# pax_counter.net
KiCad netlist of a schematic drawn in EAGLE
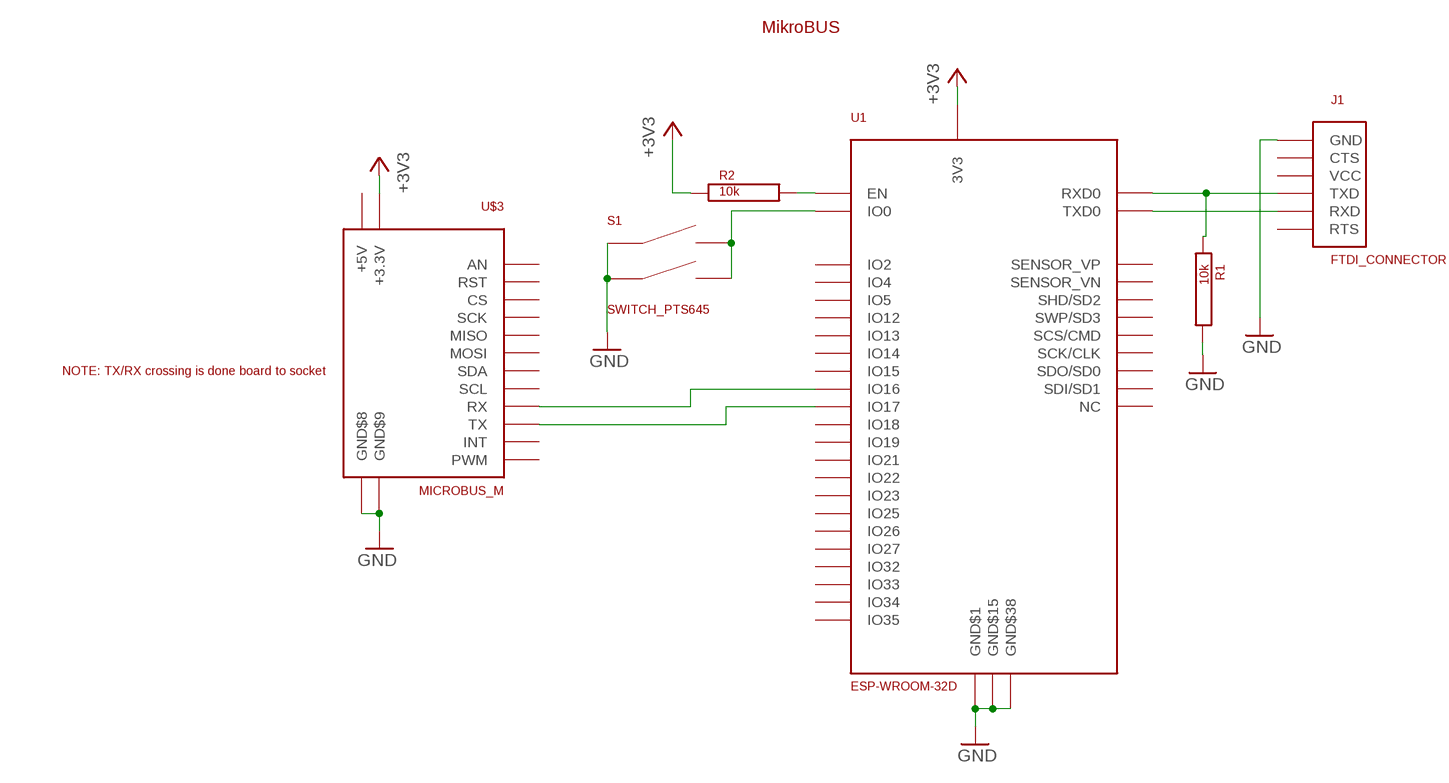
[diagram p0: schematic, sheet 1]

(export (version "E")
  (design (tool "Eeschema 10.0.6"))
  (components
    (comp (ref "J1")
      (value "FTDI_CONNECTOR")
      (footprint "eagle-import:FTDI_CONNECTOR")
      (libsource (lib "eagle-import") (part "FTDI_CONNECTOR"))
    )
    (comp (ref "R1")
      (value "10k")
      (footprint "eagle-import:RES_0402")
      (libsource (lib "eagle-import") (part "RESISTOR"))
    )
    (comp (ref "R2")
      (value "10k")
      (footprint "eagle-import:RES_0402")
      (libsource (lib "eagle-import") (part "RESISTOR"))
    )
    (comp (ref "S1")
      (value "SWITCH_PTS645")
      (footprint "eagle-import:SWITCH_PTS645_EE_NBIOT_01")
      (libsource (lib "eagle-import") (part "SWITCH_PTS645"))
    )
    (comp (ref "U$1")
      (value "MIKROBUS_LOGO")
      (footprint "eagle-import:MIKROBUS_LOGO")
      (libsource (lib "eagle-import") (part "MIKROBUS_LOGO"))
    )
    (comp (ref "U$3")
      (value "MICROBUS_M")
      (footprint "eagle-import:MIKROBUS_M")
      (libsource (lib "eagle-import") (part "MICROBUS_M"))
    )
    (comp (ref "U1")
      (value "ESP-WROOM-32D")
      (footprint "eagle-import:ESP_WROOM_32D")
      (libsource (lib "eagle-import") (part "ESP-WROOM-32D"))
    )
  )
  (nets
    (net (code "1") (name "+3V3") (class "Default")
      (node (ref "R2") (pin "P$1") (pinfunction "P$1_P$1") (pintype "bidirectional"))
      (node (ref "U$3") (pin "+3.3V") (pinfunction "+3.3V_+3.3V") (pintype "bidirectional"))
      (node (ref "U1") (pin "2") (pinfunction "3V3_2") (pintype "bidirectional"))
    )
    (net (code "2") (name "GND") (class "Default")
      (node (ref "J1") (pin "GND") (pinfunction "GND_GND") (pintype "bidirectional"))
      (node (ref "R1") (pin "P$2") (pinfunction "P$2_P$2") (pintype "bidirectional"))
      (node (ref "S1") (pin "A1") (pinfunction "A1_A1") (pintype "bidirectional"))
      (node (ref "S1") (pin "A2") (pinfunction "A2_A2") (pintype "bidirectional"))
      (node (ref "U$3") (pin "GND$8") (pinfunction "GND$8_GND$8") (pintype "bidirectional"))
      (node (ref "U$3") (pin "GND$9") (pinfunction "GND$9_GND$9") (pintype "bidirectional"))
      (node (ref "U1") (pin "1") (pinfunction "GND$1_1") (pintype "bidirectional"))
      (node (ref "U1") (pin "15") (pinfunction "GND$15_15") (pintype "bidirectional"))
      (node (ref "U1") (pin "38") (pinfunction "GND$38_38") (pintype "bidirectional"))
      (node (ref "U1") (pin "GND$39") (pinfunction "GND$38_GND$39") (pintype "bidirectional"))
      (node (ref "U1") (pin "GND$40") (pinfunction "GND$38_GND$40") (pintype "bidirectional"))
      (node (ref "U1") (pin "GND$41") (pinfunction "GND$38_GND$41") (pintype "bidirectional"))
      (node (ref "U1") (pin "GND$42") (pinfunction "GND$38_GND$42") (pintype "bidirectional"))
      (node (ref "U1") (pin "GND$43") (pinfunction "GND$38_GND$43") (pintype "bidirectional"))
      (node (ref "U1") (pin "GND$44") (pinfunction "GND$38_GND$44") (pintype "bidirectional"))
      (node (ref "U1") (pin "GND$45") (pinfunction "GND$38_GND$45") (pintype "bidirectional"))
      (node (ref "U1") (pin "GND$46") (pinfunction "GND$38_GND$46") (pintype "bidirectional"))
      (node (ref "U1") (pin "GND$47") (pinfunction "GND$38_GND$47") (pintype "bidirectional"))
    )
    (net (code "3") (name "Net-(U1-EN)") (class "Default")
      (node (ref "R2") (pin "P$2") (pinfunction "P$2_P$2") (pintype "bidirectional"))
      (node (ref "U1") (pin "3") (pinfunction "EN_3") (pintype "bidirectional"))
    )
    (net (code "4") (name "Net-(U1-IO0)") (class "Default")
      (node (ref "S1") (pin "B1") (pinfunction "B1_B1") (pintype "bidirectional"))
      (node (ref "S1") (pin "B2") (pinfunction "B2_B2") (pintype "bidirectional"))
      (node (ref "U1") (pin "25") (pinfunction "IO0_25") (pintype "bidirectional"))
    )
    (net (code "5") (name "Net-(U1-IO16)") (class "Default")
      (node (ref "U$3") (pin "RX") (pinfunction "RX_RX") (pintype "bidirectional"))
      (node (ref "U1") (pin "27") (pinfunction "IO16_27") (pintype "bidirectional"))
    )
    (net (code "6") (name "Net-(U1-IO17)") (class "Default")
      (node (ref "U$3") (pin "TX") (pinfunction "TX_TX") (pintype "bidirectional"))
      (node (ref "U1") (pin "28") (pinfunction "IO17_28") (pintype "bidirectional"))
    )
    (net (code "7") (name "Net-(U1-RXD0)") (class "Default")
      (node (ref "J1") (pin "TXD") (pinfunction "TXD_TXD") (pintype "bidirectional"))
      (node (ref "R1") (pin "P$1") (pinfunction "P$1_P$1") (pintype "bidirectional"))
      (node (ref "U1") (pin "34") (pinfunction "RXD0_34") (pintype "bidirectional"))
    )
    (net (code "8") (name "Net-(U1-TXD0)") (class "Default")
      (node (ref "J1") (pin "RXD") (pinfunction "RXD_RXD") (pintype "bidirectional"))
      (node (ref "U1") (pin "35") (pinfunction "TXD0_35") (pintype "bidirectional"))
    )
    (net (code "9") (name "unconnected-(J1-PadCTS)") (class "Default")
      (node (ref "J1") (pin "CTS") (pinfunction "CTS_CTS") (pintype "bidirectional"))
    )
    (net (code "10") (name "unconnected-(J1-PadRTS)") (class "Default")
      (node (ref "J1") (pin "RTS") (pinfunction "RTS_RTS") (pintype "bidirectional"))
    )
    (net (code "11") (name "unconnected-(J1-PadVCC)") (class "Default")
      (node (ref "J1") (pin "VCC") (pinfunction "VCC_VCC") (pintype "bidirectional"))
    )
    (net (code "12") (name "unconnected-(U$3-Pad+5V)") (class "Default")
      (node (ref "U$3") (pin "+5V") (pinfunction "+5V_+5V") (pintype "bidirectional"))
    )
    (net (code "13") (name "unconnected-(U$3-PadAN)") (class "Default")
      (node (ref "U$3") (pin "AN") (pinfunction "AN_AN") (pintype "bidirectional"))
    )
    (net (code "14") (name "unconnected-(U$3-PadCS)") (class "Default")
      (node (ref "U$3") (pin "CS") (pinfunction "CS_CS") (pintype "bidirectional"))
    )
    (net (code "15") (name "unconnected-(U$3-PadINT)") (class "Default")
      (node (ref "U$3") (pin "INT") (pinfunction "INT_INT") (pintype "bidirectional"))
    )
    (net (code "16") (name "unconnected-(U$3-PadMISO)") (class "Default")
      (node (ref "U$3") (pin "MISO") (pinfunction "MISO_MISO") (pintype "bidirectional"))
    )
    (net (code "17") (name "unconnected-(U$3-PadMOSI)") (class "Default")
      (node (ref "U$3") (pin "MOSI") (pinfunction "MOSI_MOSI") (pintype "bidirectional"))
    )
    (net (code "18") (name "unconnected-(U$3-PadPWM)") (class "Default")
      (node (ref "U$3") (pin "PWM") (pinfunction "PWM_PWM") (pintype "bidirectional"))
    )
    (net (code "19") (name "unconnected-(U$3-PadRST)") (class "Default")
      (node (ref "U$3") (pin "RST") (pinfunction "RST_RST") (pintype "bidirectional"))
    )
    (net (code "20") (name "unconnected-(U$3-PadSCK)") (class "Default")
      (node (ref "U$3") (pin "SCK") (pinfunction "SCK_SCK") (pintype "bidirectional"))
    )
    (net (code "21") (name "unconnected-(U$3-PadSCL)") (class "Default")
      (node (ref "U$3") (pin "SCL") (pinfunction "SCL_SCL") (pintype "bidirectional"))
    )
    (net (code "22") (name "unconnected-(U$3-PadSDA)") (class "Default")
      (node (ref "U$3") (pin "SDA") (pinfunction "SDA_SDA") (pintype "bidirectional"))
    )
    (net (code "23") (name "unconnected-(U1-IO2-Pad24)") (class "Default")
      (node (ref "U1") (pin "24") (pinfunction "IO2_24") (pintype "bidirectional"))
    )
    (net (code "24") (name "unconnected-(U1-IO4-Pad26)") (class "Default")
      (node (ref "U1") (pin "26") (pinfunction "IO4_26") (pintype "bidirectional"))
    )
    (net (code "25") (name "unconnected-(U1-IO5-Pad29)") (class "Default")
      (node (ref "U1") (pin "29") (pinfunction "IO5_29") (pintype "bidirectional"))
    )
    (net (code "26") (name "unconnected-(U1-IO12-Pad14)") (class "Default")
      (node (ref "U1") (pin "14") (pinfunction "IO12_14") (pintype "bidirectional"))
    )
    (net (code "27") (name "unconnected-(U1-IO13-Pad16)") (class "Default")
      (node (ref "U1") (pin "16") (pinfunction "IO13_16") (pintype "bidirectional"))
    )
    (net (code "28") (name "unconnected-(U1-IO14-Pad13)") (class "Default")
      (node (ref "U1") (pin "13") (pinfunction "IO14_13") (pintype "bidirectional"))
    )
    (net (code "29") (name "unconnected-(U1-IO15-Pad23)") (class "Default")
      (node (ref "U1") (pin "23") (pinfunction "IO15_23") (pintype "bidirectional"))
    )
    (net (code "30") (name "unconnected-(U1-IO18-Pad30)") (class "Default")
      (node (ref "U1") (pin "30") (pinfunction "IO18_30") (pintype "bidirectional"))
    )
    (net (code "31") (name "unconnected-(U1-IO19-Pad31)") (class "Default")
      (node (ref "U1") (pin "31") (pinfunction "IO19_31") (pintype "bidirectional"))
    )
    (net (code "32") (name "unconnected-(U1-IO21-Pad33)") (class "Default")
      (node (ref "U1") (pin "33") (pinfunction "IO21_33") (pintype "bidirectional"))
    )
    (net (code "33") (name "unconnected-(U1-IO22-Pad36)") (class "Default")
      (node (ref "U1") (pin "36") (pinfunction "IO22_36") (pintype "bidirectional"))
    )
    (net (code "34") (name "unconnected-(U1-IO23-Pad37)") (class "Default")
      (node (ref "U1") (pin "37") (pinfunction "IO23_37") (pintype "bidirectional"))
    )
    (net (code "35") (name "unconnected-(U1-IO25-Pad10)") (class "Default")
      (node (ref "U1") (pin "10") (pinfunction "IO25_10") (pintype "bidirectional"))
    )
    (net (code "36") (name "unconnected-(U1-IO26-Pad11)") (class "Default")
      (node (ref "U1") (pin "11") (pinfunction "IO26_11") (pintype "bidirectional"))
    )
    (net (code "37") (name "unconnected-(U1-IO27-Pad12)") (class "Default")
      (node (ref "U1") (pin "12") (pinfunction "IO27_12") (pintype "bidirectional"))
    )
    (net (code "38") (name "unconnected-(U1-IO32-Pad8)") (class "Default")
      (node (ref "U1") (pin "8") (pinfunction "IO32_8") (pintype "bidirectional"))
    )
    (net (code "39") (name "unconnected-(U1-IO33-Pad9)") (class "Default")
      (node (ref "U1") (pin "9") (pinfunction "IO33_9") (pintype "bidirectional"))
    )
    (net (code "40") (name "unconnected-(U1-IO34-Pad6)") (class "Default")
      (node (ref "U1") (pin "6") (pinfunction "IO34_6") (pintype "bidirectional"))
    )
    (net (code "41") (name "unconnected-(U1-IO35-Pad7)") (class "Default")
      (node (ref "U1") (pin "7") (pinfunction "IO35_7") (pintype "bidirectional"))
    )
    (net (code "42") (name "unconnected-(U1-NC-Pad32)") (class "Default")
      (node (ref "U1") (pin "32") (pinfunction "NC_32") (pintype "bidirectional"))
    )
    (net (code "43") (name "unconnected-(U1-SCK{slash}CLK-Pad20)") (class "Default")
      (node (ref "U1") (pin "20") (pinfunction "SCK/CLK_20") (pintype "bidirectional"))
    )
    (net (code "44") (name "unconnected-(U1-SCS{slash}CMD-Pad19)") (class "Default")
      (node (ref "U1") (pin "19") (pinfunction "SCS/CMD_19") (pintype "bidirectional"))
    )
    (net (code "45") (name "unconnected-(U1-SDI{slash}SD1-Pad22)") (class "Default")
      (node (ref "U1") (pin "22") (pinfunction "SDI/SD1_22") (pintype "bidirectional"))
    )
    (net (code "46") (name "unconnected-(U1-SDO{slash}SD0-Pad21)") (class "Default")
      (node (ref "U1") (pin "21") (pinfunction "SDO/SD0_21") (pintype "bidirectional"))
    )
    (net (code "47") (name "unconnected-(U1-SENSOR_VN-Pad5)") (class "Default")
      (node (ref "U1") (pin "5") (pinfunction "SENSOR_VN_5") (pintype "bidirectional"))
    )
    (net (code "48") (name "unconnected-(U1-SENSOR_VP-Pad4)") (class "Default")
      (node (ref "U1") (pin "4") (pinfunction "SENSOR_VP_4") (pintype "bidirectional"))
    )
    (net (code "49") (name "unconnected-(U1-SHD{slash}SD2-Pad17)") (class "Default")
      (node (ref "U1") (pin "17") (pinfunction "SHD/SD2_17") (pintype "bidirectional"))
    )
    (net (code "50") (name "unconnected-(U1-SWP{slash}SD3-Pad18)") (class "Default")
      (node (ref "U1") (pin "18") (pinfunction "SWP/SD3_18") (pintype "bidirectional"))
    )
  )
)
